# ProPrj__OPA695_2025-07-24.net
KiCad netlist of a schematic drawn in EasyEDA Pro
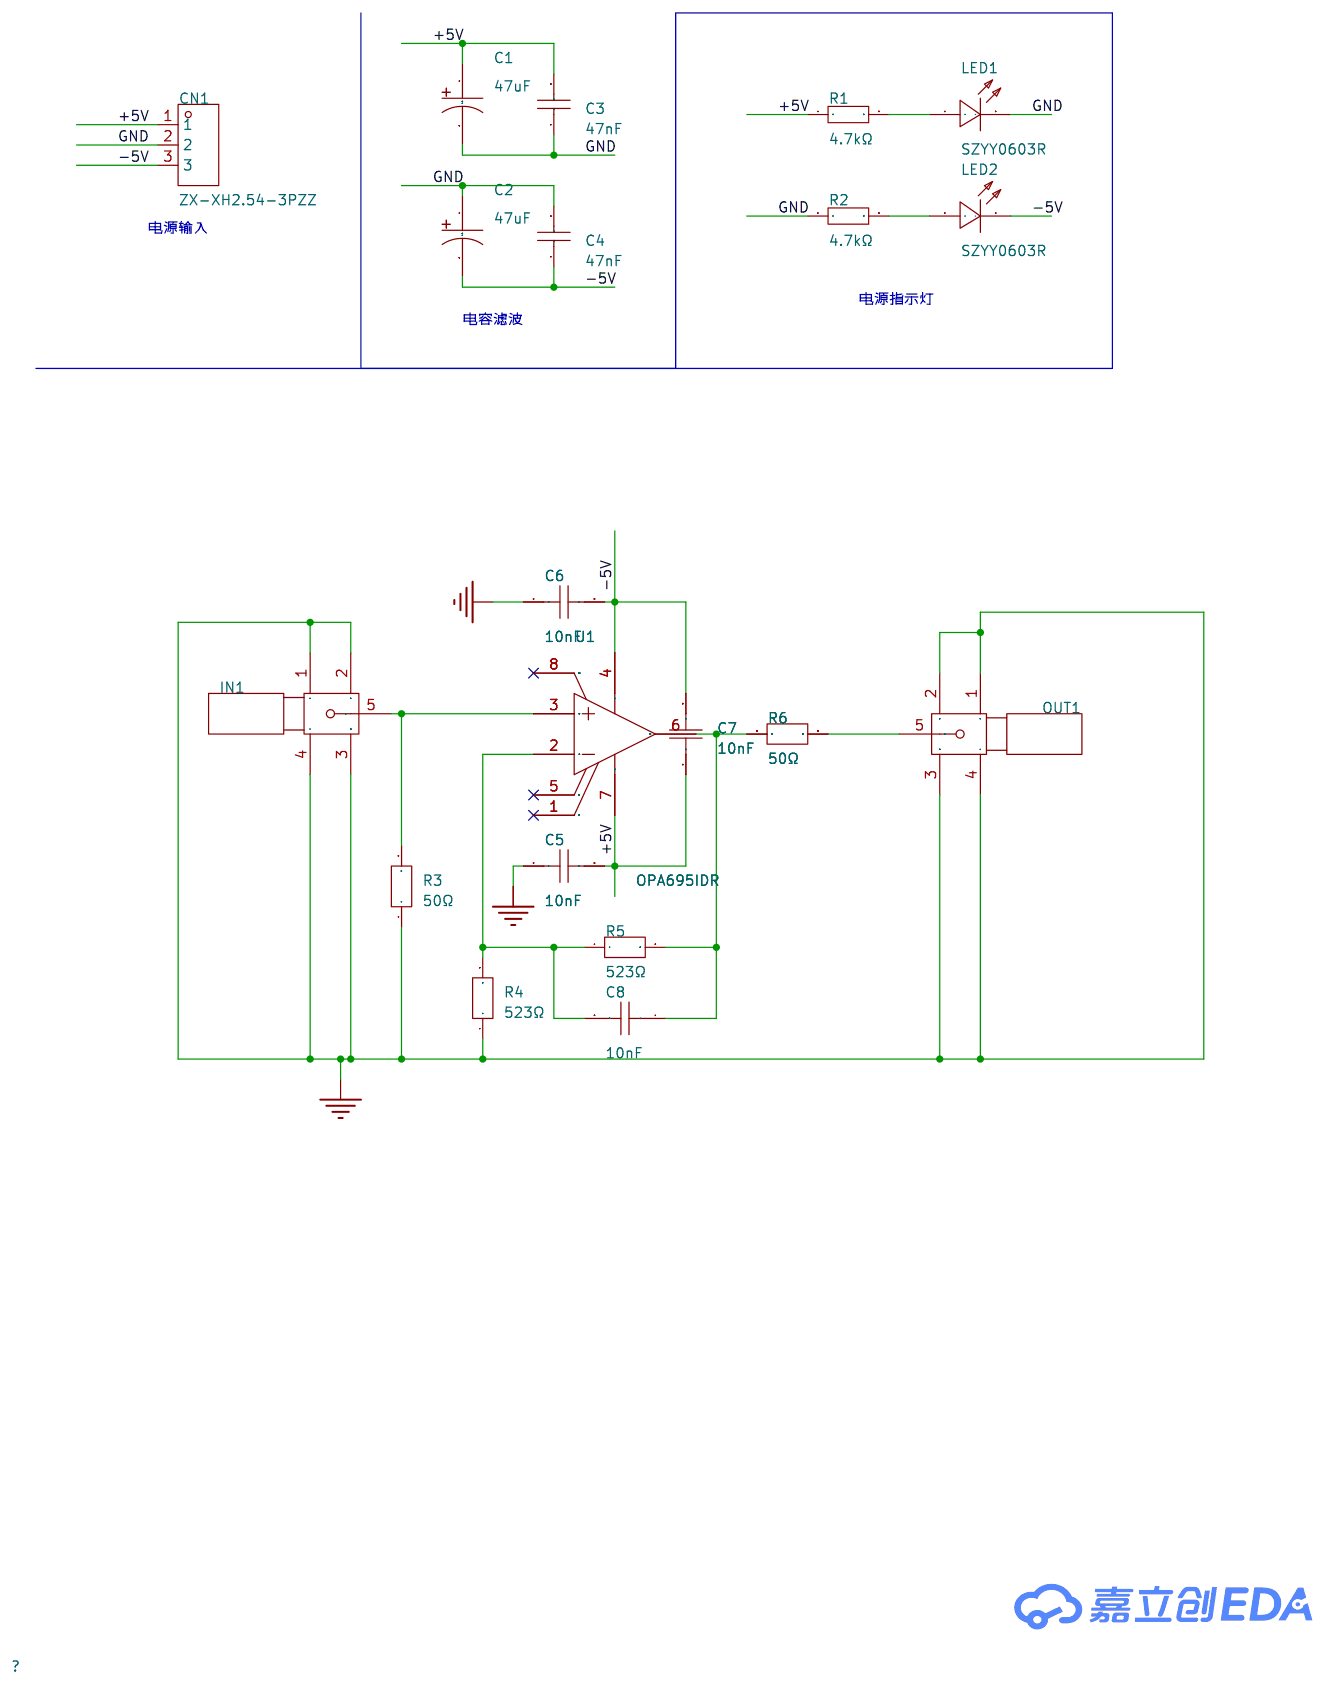
[diagram p0: schematic sheet]

(export (version "E")
  (design (tool "Eeschema 10.0.6"))
  (components
    (comp (ref "C1")
      (value "47uF")
      (footprint "easyedapro:CAP-TH_BD5.0-P2.00-D0.8-FD")
      (description "容值:47uF;精度:±20%;额定电压:25V;纹波电流:250mA@100kHz;等效串联电阻(ESR):300mΩ@100kHz;")
      (fields
        (field (name "Manufacturer Part") "NXB25V47M5*11 2.5TP")
        (field (name "Manufacturer") "SAMYOUNG(韩国三莹)")
      )
      (libsource (lib "easyedapro") (part "NXB25VB47M5*11_2.5TP"))
    )
    (comp (ref "C2")
      (value "47uF")
      (footprint "easyedapro:CAP-TH_BD5.0-P2.00-D0.8-FD")
      (description "容值:47uF;精度:±20%;额定电压:25V;纹波电流:250mA@100kHz;等效串联电阻(ESR):300mΩ@100kHz;")
      (fields
        (field (name "Manufacturer Part") "NXB25V47M5*11 2.5TP")
        (field (name "Manufacturer") "SAMYOUNG(韩国三莹)")
      )
      (libsource (lib "easyedapro") (part "NXB25VB47M5*11_2.5TP"))
    )
    (comp (ref "C3")
      (value "47nF")
      (footprint "easyedapro:C0805")
      (description "容值:47nF;精度:±10%;额定电压:50V;材质(温度系数):X7R;")
      (fields
        (field (name "Manufacturer Part") "CL21B473KBCNNNC")
        (field (name "Manufacturer") "SAMSUNG(三星)")
      )
      (libsource (lib "easyedapro") (part "CL21B473KBCNNNC"))
    )
    (comp (ref "C4")
      (value "47nF")
      (footprint "easyedapro:C0805")
      (description "容值:47nF;精度:±10%;额定电压:50V;材质(温度系数):X7R;")
      (fields
        (field (name "Manufacturer Part") "CL21B473KBCNNNC")
        (field (name "Manufacturer") "SAMSUNG(三星)")
      )
      (libsource (lib "easyedapro") (part "CL21B473KBCNNNC"))
    )
    (comp (ref "C5")
      (value "10nF")
      (footprint "easyedapro:C0805")
      (description "容值:10nF;精度:±10%;额定电压:50V;材质(温度系数):X7R;")
      (fields
        (field (name "Manufacturer Part") "CC0805KRX7R9BB103")
        (field (name "Manufacturer") "YAGEO(国巨)")
      )
      (libsource (lib "easyedapro") (part "CC0805KRX7R9BB103"))
    )
    (comp (ref "C6")
      (value "10nF")
      (footprint "easyedapro:C0805")
      (description "容值:10nF;精度:±10%;额定电压:50V;材质(温度系数):X7R;")
      (fields
        (field (name "Manufacturer Part") "CC0805KRX7R9BB103")
        (field (name "Manufacturer") "YAGEO(国巨)")
      )
      (libsource (lib "easyedapro") (part "CC0805KRX7R9BB103"))
    )
    (comp (ref "C7")
      (value "10nF")
      (footprint "easyedapro:C0805")
      (description "容值:10nF;精度:±10%;额定电压:50V;材质(温度系数):X7R;")
      (fields
        (field (name "Manufacturer Part") "CC0805KRX7R9BB103")
        (field (name "Manufacturer") "YAGEO(国巨)")
      )
      (libsource (lib "easyedapro") (part "CC0805KRX7R9BB103"))
    )
    (comp (ref "C8")
      (value "10nF")
      (footprint "easyedapro:C0805")
      (description "容值:10nF;精度:±10%;额定电压:50V;材质(温度系数):X7R;")
      (fields
        (field (name "Manufacturer Part") "CC0805KRX7R9BB103")
        (field (name "Manufacturer") "YAGEO(国巨)")
      )
      (libsource (lib "easyedapro") (part "CC0805KRX7R9BB103"))
    )
    (comp (ref "CN1")
      (value "ZX-XH2.54-3PZZ")
      (footprint "easyedapro:CONN-TH_3P-P2.54_2501S-3P")
      (fields (field (name "Manufacturer") "Megastar(兆星)"))
      (libsource (lib "easyedapro") (part "ZX-XH2.54-3PZZ"))
    )
    (comp (ref "IN1")
      (value "-")
      (footprint "easyedapro:SMA-SMD_BWSMA-KE-P001")
      (description "连接器类型:板端;接口类型:内孔;端口数量:1;接口直径:5.2mm;接口长度/高度:-;频率:-;射频系列:SMA;阻抗:50Ω;样式:偏脚;工作温度:-;")
      (fields
        (field (name "Manufacturer Part") "BWSMA-KE-P001")
        (field (name "Manufacturer") "BAT WIRELESS(蝙蝠无线)")
      )
      (libsource (lib "easyedapro") (part "BWSMA-KE-P001"))
    )
    (comp (ref "LED1")
      (value "SZYY0603R")
      (footprint "easyedapro:LED0603-R-RD")
      (fields (field (name "Manufacturer") "yongyu(永裕光电)"))
      (libsource (lib "easyedapro") (part "SZYY0603R"))
    )
    (comp (ref "LED2")
      (value "SZYY0603R")
      (footprint "easyedapro:LED0603-R-RD")
      (fields (field (name "Manufacturer") "yongyu(永裕光电)"))
      (libsource (lib "easyedapro") (part "SZYY0603R"))
    )
    (comp (ref "OUT1")
      (value "-")
      (footprint "easyedapro:SMA-SMD_BWSMA-KE-P001")
      (description "连接器类型:板端;接口类型:内孔;端口数量:1;接口直径:5.2mm;接口长度/高度:-;频率:-;射频系列:SMA;阻抗:50Ω;样式:偏脚;工作温度:-;")
      (fields
        (field (name "Manufacturer Part") "BWSMA-KE-P001")
        (field (name "Manufacturer") "BAT WIRELESS(蝙蝠无线)")
      )
      (libsource (lib "easyedapro") (part "BWSMA-KE-P001"))
    )
    (comp (ref "R1")
      (value "4.7kΩ")
      (footprint "easyedapro:R0805")
      (description "电阻类型:厚膜电阻;阻值:4.7kΩ;精度:±1%;功率:125mW;最大工作电压:150V;温度系数:±100ppm/°C;")
      (fields
        (field (name "Manufacturer Part") "0805W8F4701T5E")
        (field (name "Manufacturer") "UNI-ROYAL(厚声)")
      )
      (libsource (lib "easyedapro") (part "0805W8F4701T5E"))
    )
    (comp (ref "R2")
      (value "4.7kΩ")
      (footprint "easyedapro:R0805")
      (description "电阻类型:厚膜电阻;阻值:4.7kΩ;精度:±1%;功率:125mW;最大工作电压:150V;温度系数:±100ppm/°C;")
      (fields
        (field (name "Manufacturer Part") "0805W8F4701T5E")
        (field (name "Manufacturer") "UNI-ROYAL(厚声)")
      )
      (libsource (lib "easyedapro") (part "0805W8F4701T5E"))
    )
    (comp (ref "R3")
      (value "50Ω")
      (footprint "easyedapro:R0805")
      (description "电阻类型:薄膜电阻;阻值:50Ω;精度:±1%;功率:125mW;最大工作电压:150V;温度系数:±25ppm/°C;")
      (fields (field (name "Manufacturer Part") "ARG05FTC0500") (field (name "Manufacturer") "Viking(光颉)"))
      (libsource (lib "easyedapro") (part "ARG05FTC0500"))
    )
    (comp (ref "R4")
      (value "523Ω")
      (footprint "easyedapro:R0805")
      (description "电阻类型:薄膜电阻;阻值:523Ω;精度:±0.1%;功率:130mW;工作电压:150V;温度系数:±25ppm/°C;")
      (fields (field (name "Manufacturer Part") "PTFR0805B523RP9") (field (name "Manufacturer") "RESI(开步睿思)"))
      (libsource (lib "easyedapro") (part "PTFR0805B523RP9"))
    )
    (comp (ref "R5")
      (value "523Ω")
      (footprint "easyedapro:R0805")
      (description "电阻类型:薄膜电阻;阻值:523Ω;精度:±0.1%;功率:130mW;工作电压:150V;温度系数:±25ppm/°C;")
      (fields (field (name "Manufacturer Part") "PTFR0805B523RP9") (field (name "Manufacturer") "RESI(开步睿思)"))
      (libsource (lib "easyedapro") (part "PTFR0805B523RP9"))
    )
    (comp (ref "R6")
      (value "50Ω")
      (footprint "easyedapro:R0805")
      (description "电阻类型:薄膜电阻;阻值:50Ω;精度:±1%;功率:125mW;最大工作电压:150V;温度系数:±25ppm/°C;")
      (fields (field (name "Manufacturer Part") "ARG05FTC0500") (field (name "Manufacturer") "Viking(光颉)"))
      (libsource (lib "easyedapro") (part "ARG05FTC0500"))
    )
    (comp (ref "U1")
      (value "OPA695IDR")
      (footprint "easyedapro:SOIC-8_L5.0-W4.0-P1.27-LS6.1-BL")
      (description "放大器数:单路;增益带宽积(GBP):-;压摆率(SR):4.3V/ns;输入偏置电流(Ib):20uA;")
      (fields (field (name "Manufacturer") "TI(德州仪器)"))
      (libsource (lib "easyedapro") (part "OPA695IDR"))
    )
  )
  (nets
    (net (code "1") (name "/+5V") (class "Default")
      (node (ref "C1") (pin "1") (pinfunction "1_1") (pintype "unspecified"))
      (node (ref "C3") (pin "2") (pinfunction "2_2") (pintype "input"))
      (node (ref "C5") (pin "2") (pinfunction "2_2") (pintype "unspecified"))
      (node (ref "C7") (pin "1") (pinfunction "1_1") (pintype "unspecified"))
      (node (ref "CN1") (pin "1") (pinfunction "1_1") (pintype "unspecified"))
      (node (ref "R1") (pin "1") (pinfunction "1_1") (pintype "input"))
      (node (ref "U1") (pin "7") (pinfunction "+VS_7") (pintype "unspecified"))
    )
    (net (code "2") (name "/-5V") (class "Default")
      (node (ref "C2") (pin "2") (pinfunction "2_2") (pintype "unspecified"))
      (node (ref "C4") (pin "1") (pinfunction "1_1") (pintype "input"))
      (node (ref "C6") (pin "2") (pinfunction "2_2") (pintype "unspecified"))
      (node (ref "C7") (pin "2") (pinfunction "2_2") (pintype "unspecified"))
      (node (ref "CN1") (pin "3") (pinfunction "3_3") (pintype "unspecified"))
      (node (ref "LED2") (pin "2") (pinfunction "-_2") (pintype "unspecified"))
      (node (ref "U1") (pin "4") (pinfunction "-VS_4") (pintype "unspecified"))
    )
    (net (code "3") (name "GND") (class "Default")
      (node (ref "C1") (pin "2") (pinfunction "2_2") (pintype "unspecified"))
      (node (ref "C2") (pin "1") (pinfunction "1_1") (pintype "unspecified"))
      (node (ref "C3") (pin "1") (pinfunction "1_1") (pintype "input"))
      (node (ref "C4") (pin "2") (pinfunction "2_2") (pintype "input"))
      (node (ref "C5") (pin "1") (pinfunction "1_1") (pintype "unspecified"))
      (node (ref "C6") (pin "1") (pinfunction "1_1") (pintype "unspecified"))
      (node (ref "CN1") (pin "2") (pinfunction "2_2") (pintype "unspecified"))
      (node (ref "IN1") (pin "1") (pinfunction "1_1") (pintype "unspecified"))
      (node (ref "IN1") (pin "2") (pinfunction "2_2") (pintype "unspecified"))
      (node (ref "IN1") (pin "3") (pinfunction "3_3") (pintype "unspecified"))
      (node (ref "IN1") (pin "4") (pinfunction "4_4") (pintype "unspecified"))
      (node (ref "LED1") (pin "2") (pinfunction "-_2") (pintype "unspecified"))
      (node (ref "OUT1") (pin "1") (pinfunction "1_1") (pintype "unspecified"))
      (node (ref "OUT1") (pin "2") (pinfunction "2_2") (pintype "unspecified"))
      (node (ref "OUT1") (pin "3") (pinfunction "3_3") (pintype "unspecified"))
      (node (ref "OUT1") (pin "4") (pinfunction "4_4") (pintype "unspecified"))
      (node (ref "R2") (pin "1") (pinfunction "1_1") (pintype "input"))
      (node (ref "R3") (pin "1") (pinfunction "1_1") (pintype "unspecified"))
      (node (ref "R4") (pin "1") (pinfunction "1_1") (pintype "unspecified"))
    )
    (net (code "4") (name "Net-(LED1-+)") (class "Default")
      (node (ref "LED1") (pin "1") (pinfunction "+_1") (pintype "unspecified"))
      (node (ref "R1") (pin "2") (pinfunction "2_2") (pintype "input"))
    )
    (net (code "5") (name "Net-(LED2-+)") (class "Default")
      (node (ref "LED2") (pin "1") (pinfunction "+_1") (pintype "unspecified"))
      (node (ref "R2") (pin "2") (pinfunction "2_2") (pintype "input"))
    )
    (net (code "6") (name "Net-(OUT1-Pad5)") (class "Default")
      (node (ref "OUT1") (pin "5") (pinfunction "5_5") (pintype "unspecified"))
      (node (ref "R6") (pin "2") (pinfunction "2_2") (pintype "unspecified"))
    )
    (net (code "7") (name "Net-(U1-+IN)") (class "Default")
      (node (ref "IN1") (pin "5") (pinfunction "5_5") (pintype "unspecified"))
      (node (ref "R3") (pin "2") (pinfunction "2_2") (pintype "unspecified"))
      (node (ref "U1") (pin "3") (pinfunction "+IN_3") (pintype "unspecified"))
    )
    (net (code "8") (name "Net-(U1--IN)") (class "Default")
      (node (ref "C8") (pin "2") (pinfunction "2_2") (pintype "unspecified"))
      (node (ref "R4") (pin "2") (pinfunction "2_2") (pintype "unspecified"))
      (node (ref "R5") (pin "1") (pinfunction "1_1") (pintype "unspecified"))
      (node (ref "U1") (pin "2") (pinfunction "-IN_2") (pintype "unspecified"))
    )
    (net (code "9") (name "Net-(U1-Output)") (class "Default")
      (node (ref "C8") (pin "1") (pinfunction "1_1") (pintype "unspecified"))
      (node (ref "R5") (pin "2") (pinfunction "2_2") (pintype "unspecified"))
      (node (ref "R6") (pin "1") (pinfunction "1_1") (pintype "unspecified"))
      (node (ref "U1") (pin "6") (pinfunction "Output_6") (pintype "output"))
    )
    (net (code "10") (name "unconnected-(U1-DIS#-Pad8)") (class "Default")
      (node (ref "U1") (pin "8") (pinfunction "DIS#_8") (pintype "unspecified+no_connect"))
    )
    (net (code "11") (name "unconnected-(U1-NC-Pad1)") (class "Default")
      (node (ref "U1") (pin "1") (pinfunction "NC_1") (pintype "unspecified+no_connect"))
    )
    (net (code "12") (name "unconnected-(U1-NC-Pad5)") (class "Default")
      (node (ref "U1") (pin "5") (pinfunction "NC_5") (pintype "unspecified+no_connect"))
    )
  )
)
